# SCH-typeC.net
KiCad netlist of a schematic drawn in EasyEDA
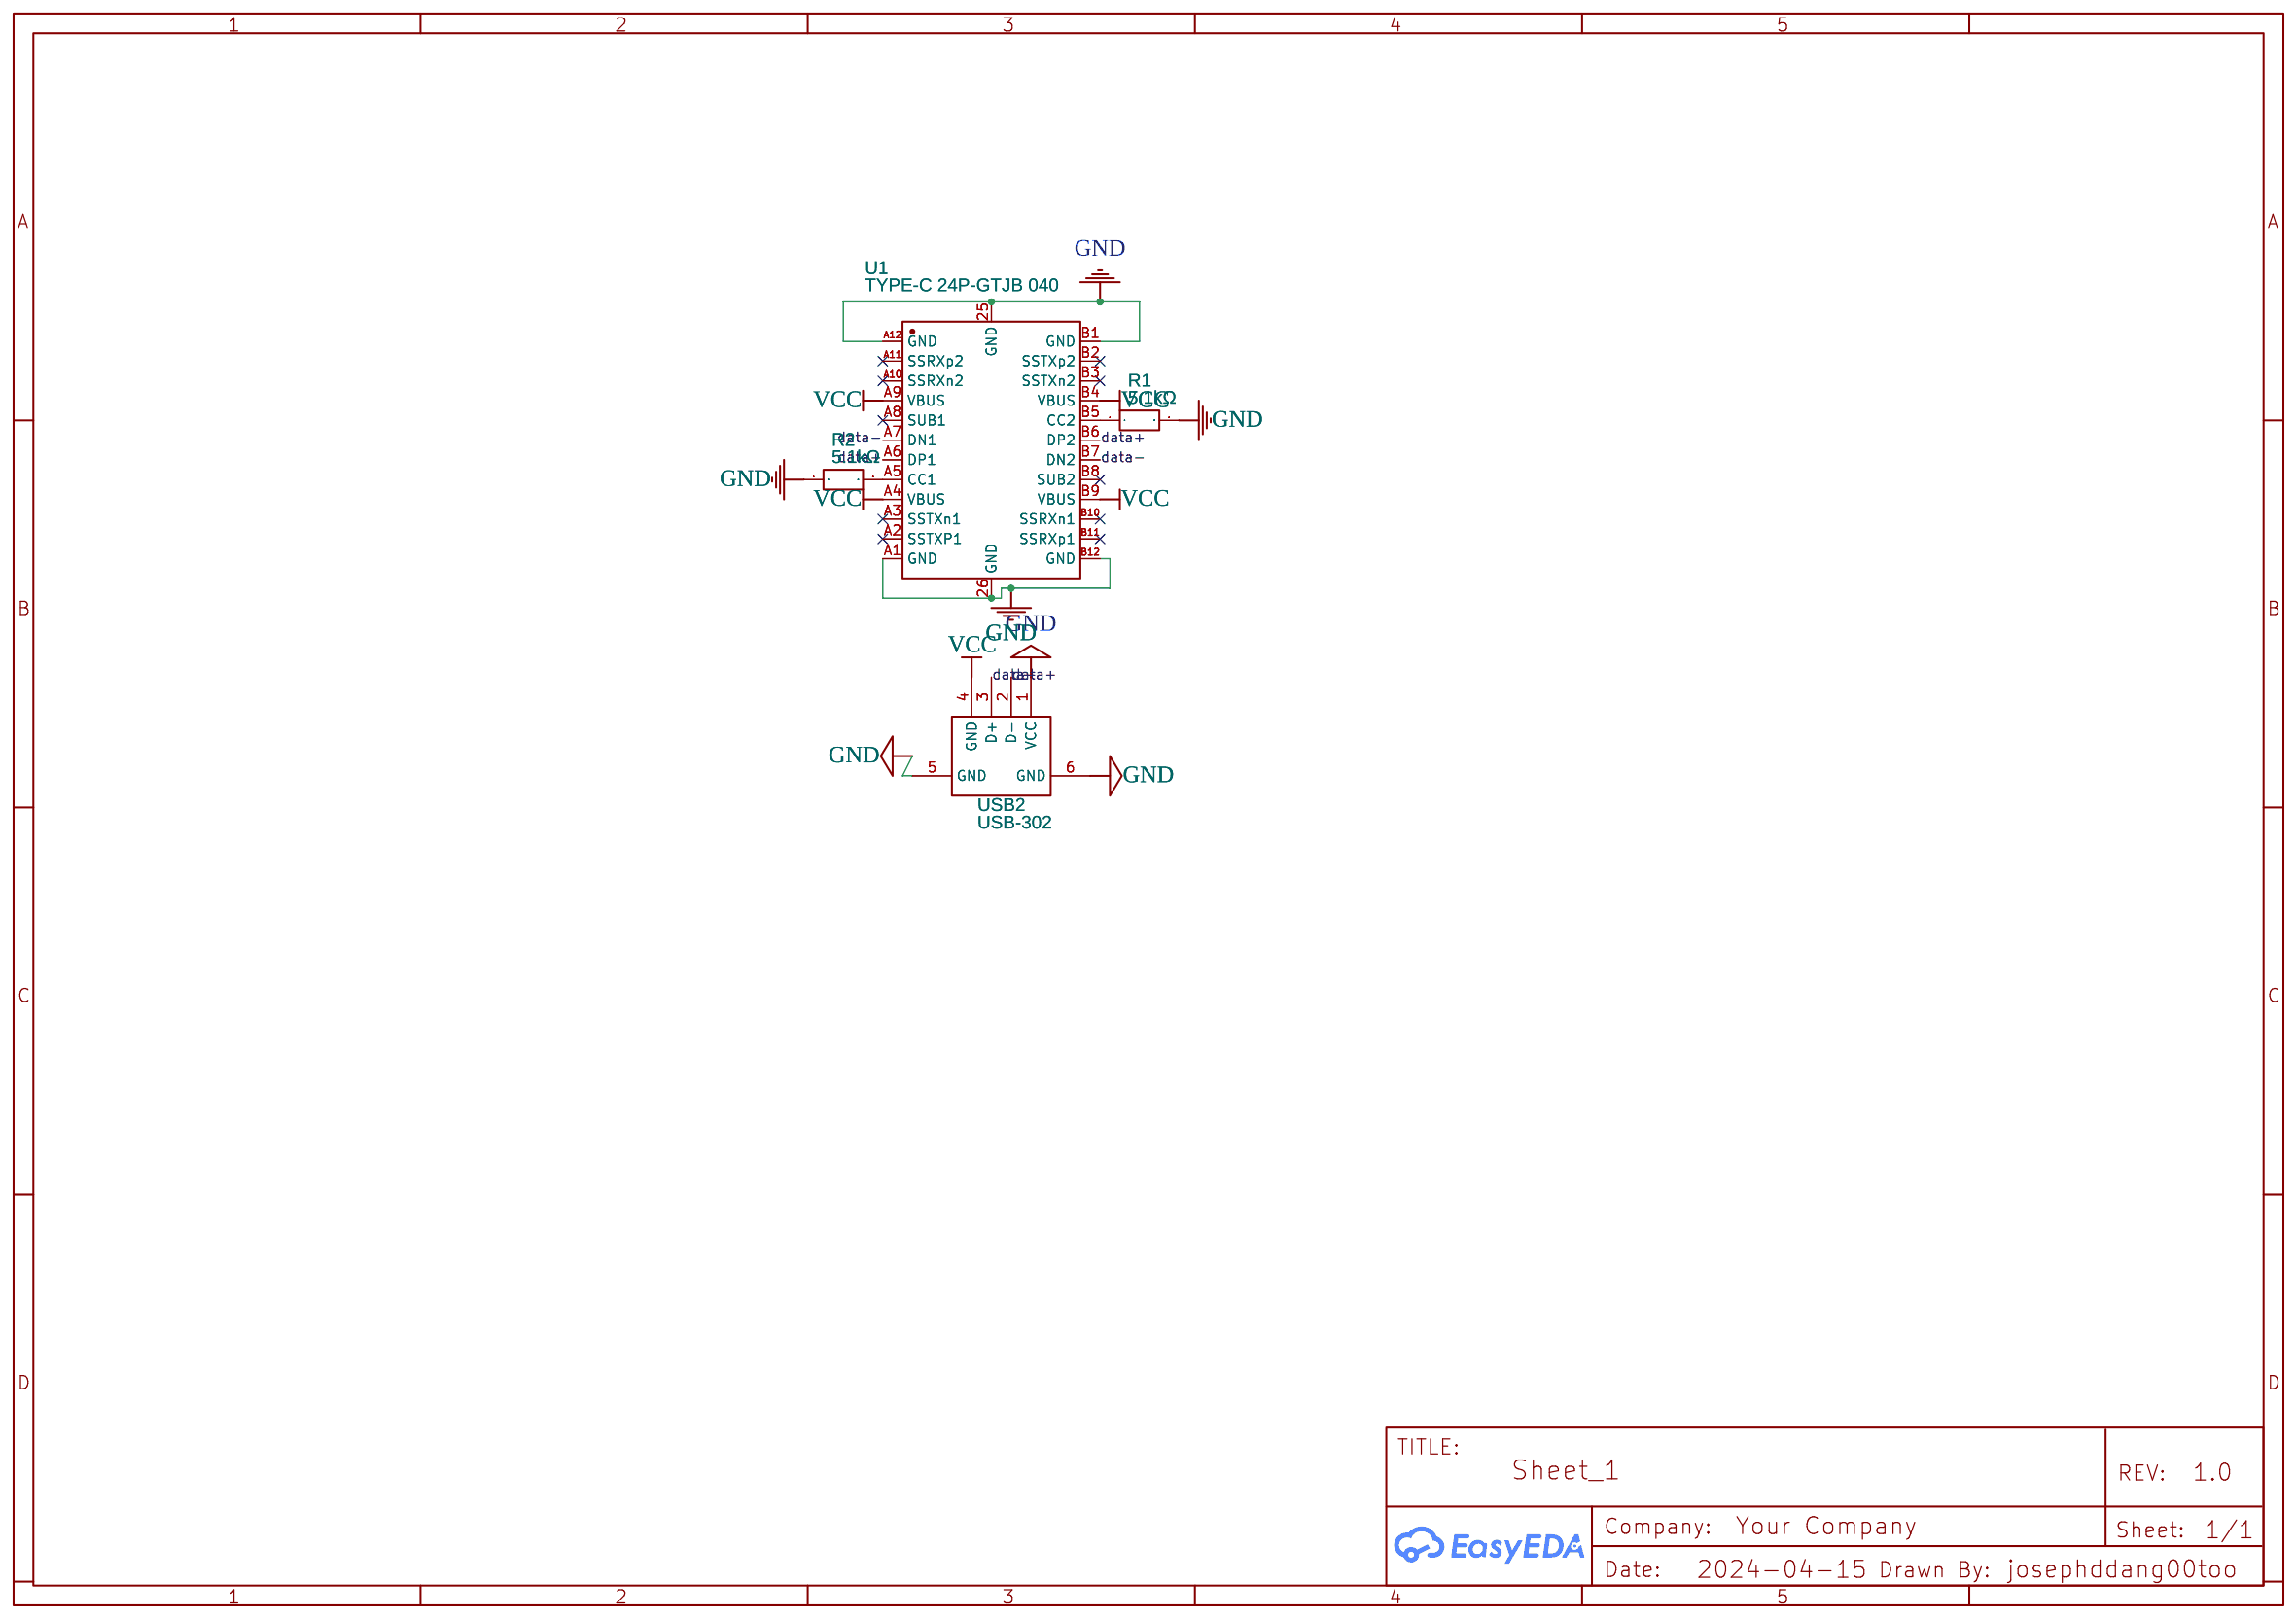
[diagram p0: schematic sheet]

(export (version "E")
  (design (tool "Eeschema 10.0.6"))
  (components
    (comp (ref "R1")
      (value "5.1kΩ")
      (fields
        (field (name "Manufacturer Part") "NQ05W8F5101T5E")
        (field (name "Manufacturer") "UNI-ROYAL(厚声)")
      )
      (libsource (lib "") (part "NQ05W8F5101T5E"))
    )
    (comp (ref "R2")
      (value "5.1kΩ")
      (fields
        (field (name "Manufacturer Part") "NQ05W8F5101T5E")
        (field (name "Manufacturer") "UNI-ROYAL(厚声)")
      )
      (libsource (lib "") (part "NQ05W8F5101T5E"))
    )
    (comp (ref "U1")
      (value "TYPE-C 24P-GTJB 040")
      (fields (field (name "Manufacturer") "SHOU HAN(首韩)"))
      (libsource (lib "") (part "TYPE-C 24P-GTJB 040"))
    )
    (comp (ref "USB2")
      (value "USB-302")
      (fields (field (name "Manufacturer Part") "USB-302-T") (field (name "Manufacturer") "SOFNG(硕方)"))
      (libsource (lib "") (part "USB-302"))
    )
  )
  (nets
    (net (code "1") (name "/data+") (class "Default")
      (node (ref "U1") (pin "A6") (pinfunction "DP1_A6") (pintype "unspecified"))
      (node (ref "U1") (pin "B6") (pinfunction "DP2_B6") (pintype "unspecified"))
      (node (ref "USB2") (pin "2") (pinfunction "D-_2") (pintype "unspecified"))
    )
    (net (code "2") (name "/data-") (class "Default")
      (node (ref "U1") (pin "A7") (pinfunction "DN1_A7") (pintype "unspecified"))
      (node (ref "U1") (pin "B7") (pinfunction "DN2_B7") (pintype "unspecified"))
      (node (ref "USB2") (pin "3") (pinfunction "D+_3") (pintype "unspecified"))
    )
    (net (code "3") (name "GND") (class "Default")
      (node (ref "R1") (pin "2") (pinfunction "2_2") (pintype "unspecified"))
      (node (ref "R2") (pin "1") (pinfunction "1_1") (pintype "unspecified"))
      (node (ref "U1") (pin "25") (pinfunction "GND_25") (pintype "unspecified"))
      (node (ref "U1") (pin "26") (pinfunction "GND_26") (pintype "unspecified"))
      (node (ref "U1") (pin "A1") (pinfunction "GND_A1") (pintype "unspecified"))
      (node (ref "U1") (pin "A12") (pinfunction "GND_A12") (pintype "unspecified"))
      (node (ref "U1") (pin "B1") (pinfunction "GND_B1") (pintype "unspecified"))
      (node (ref "U1") (pin "B12") (pinfunction "GND_B12") (pintype "unspecified"))
      (node (ref "USB2") (pin "1") (pinfunction "VCC_1") (pintype "unspecified"))
      (node (ref "USB2") (pin "5") (pinfunction "GND_5") (pintype "unspecified"))
      (node (ref "USB2") (pin "6") (pinfunction "GND_6") (pintype "unspecified"))
    )
    (net (code "4") (name "Net-(U1-CC1)") (class "Default")
      (node (ref "R2") (pin "2") (pinfunction "2_2") (pintype "unspecified"))
      (node (ref "U1") (pin "A5") (pinfunction "CC1_A5") (pintype "unspecified"))
    )
    (net (code "5") (name "Net-(U1-CC2)") (class "Default")
      (node (ref "R1") (pin "1") (pinfunction "1_1") (pintype "unspecified"))
      (node (ref "U1") (pin "B5") (pinfunction "CC2_B5") (pintype "unspecified"))
    )
    (net (code "6") (name "VCC") (class "Default")
      (node (ref "U1") (pin "A4") (pinfunction "VBUS_A4") (pintype "unspecified"))
      (node (ref "U1") (pin "A9") (pinfunction "VBUS_A9") (pintype "unspecified"))
      (node (ref "U1") (pin "B4") (pinfunction "VBUS_B4") (pintype "unspecified"))
      (node (ref "U1") (pin "B9") (pinfunction "VBUS_B9") (pintype "unspecified"))
      (node (ref "USB2") (pin "4") (pinfunction "GND_4") (pintype "unspecified"))
    )
    (net (code "7") (name "unconnected-(U1-SSRXn1-PadB10)") (class "Default")
      (node (ref "U1") (pin "B10") (pinfunction "SSRXn1_B10") (pintype "unspecified+no_connect"))
    )
    (net (code "8") (name "unconnected-(U1-SSRXn2-PadA10)") (class "Default")
      (node (ref "U1") (pin "A10") (pinfunction "SSRXn2_A10") (pintype "unspecified+no_connect"))
    )
    (net (code "9") (name "unconnected-(U1-SSRXp1-PadB11)") (class "Default")
      (node (ref "U1") (pin "B11") (pinfunction "SSRXp1_B11") (pintype "unspecified+no_connect"))
    )
    (net (code "10") (name "unconnected-(U1-SSRXp2-PadA11)") (class "Default")
      (node (ref "U1") (pin "A11") (pinfunction "SSRXp2_A11") (pintype "unspecified+no_connect"))
    )
    (net (code "11") (name "unconnected-(U1-SSTXP1-PadA2)") (class "Default")
      (node (ref "U1") (pin "A2") (pinfunction "SSTXP1_A2") (pintype "unspecified+no_connect"))
    )
    (net (code "12") (name "unconnected-(U1-SSTXn1-PadA3)") (class "Default")
      (node (ref "U1") (pin "A3") (pinfunction "SSTXn1_A3") (pintype "unspecified+no_connect"))
    )
    (net (code "13") (name "unconnected-(U1-SSTXn2-PadB3)") (class "Default")
      (node (ref "U1") (pin "B3") (pinfunction "SSTXn2_B3") (pintype "unspecified+no_connect"))
    )
    (net (code "14") (name "unconnected-(U1-SSTXp2-PadB2)") (class "Default")
      (node (ref "U1") (pin "B2") (pinfunction "SSTXp2_B2") (pintype "unspecified+no_connect"))
    )
    (net (code "15") (name "unconnected-(U1-SUB1-PadA8)") (class "Default")
      (node (ref "U1") (pin "A8") (pinfunction "SUB1_A8") (pintype "unspecified+no_connect"))
    )
    (net (code "16") (name "unconnected-(U1-SUB2-PadB8)") (class "Default")
      (node (ref "U1") (pin "B8") (pinfunction "SUB2_B8") (pintype "unspecified+no_connect"))
    )
  )
)
